# ESC_BOARD.net
KiCad netlist of a schematic drawn in EAGLE
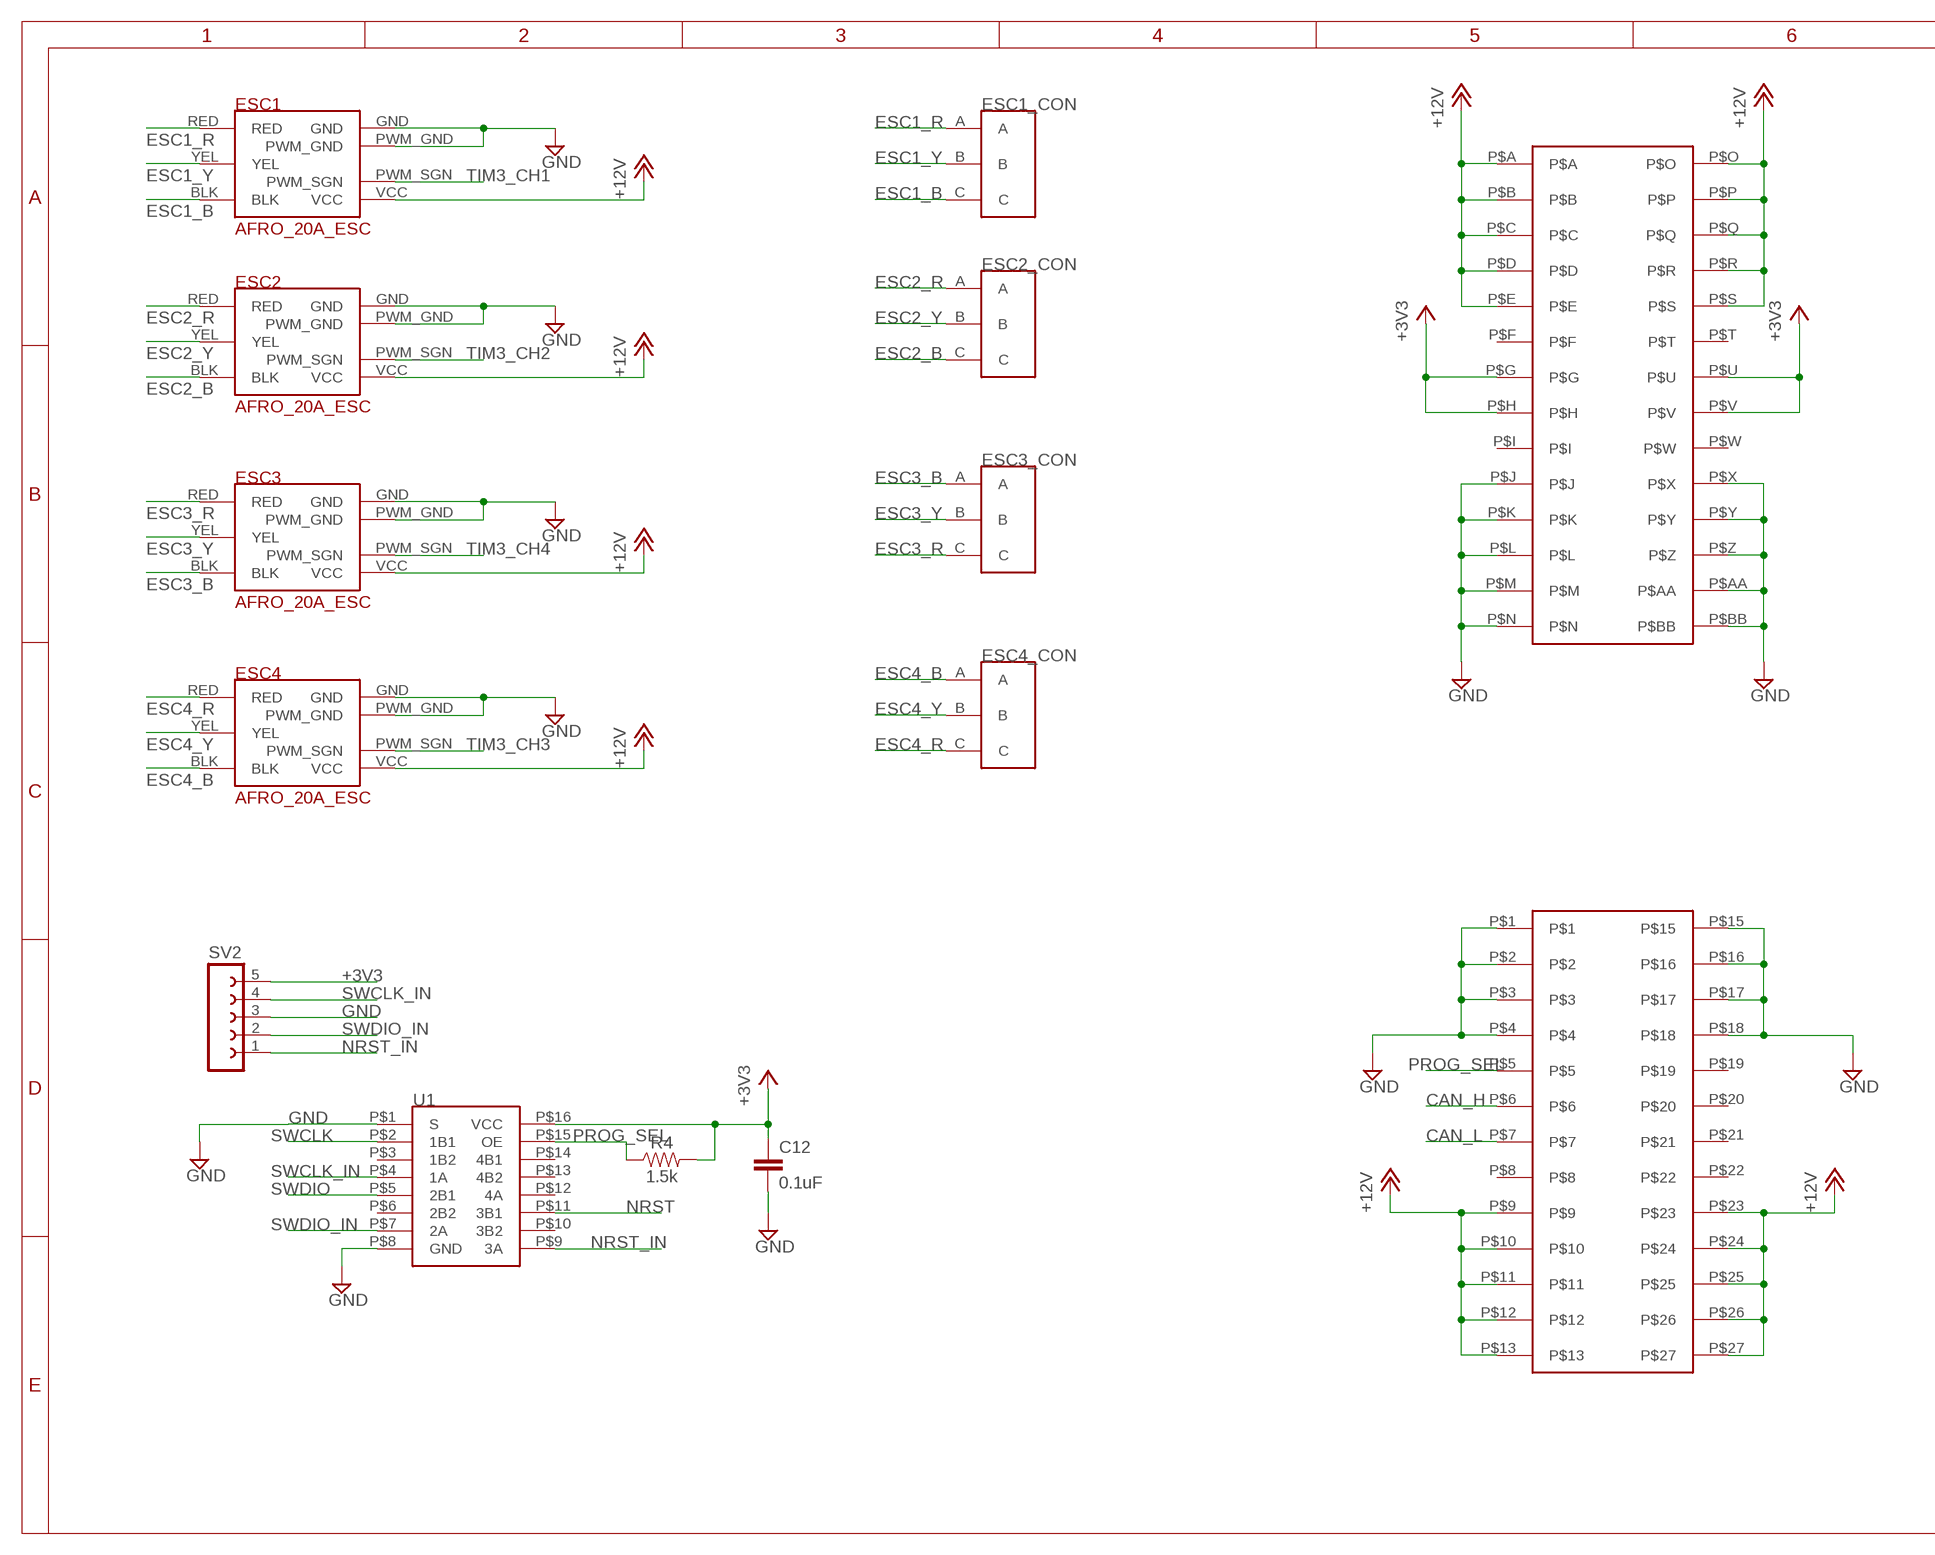
[diagram p0: schematic, sheet 1, part 1 of 2]
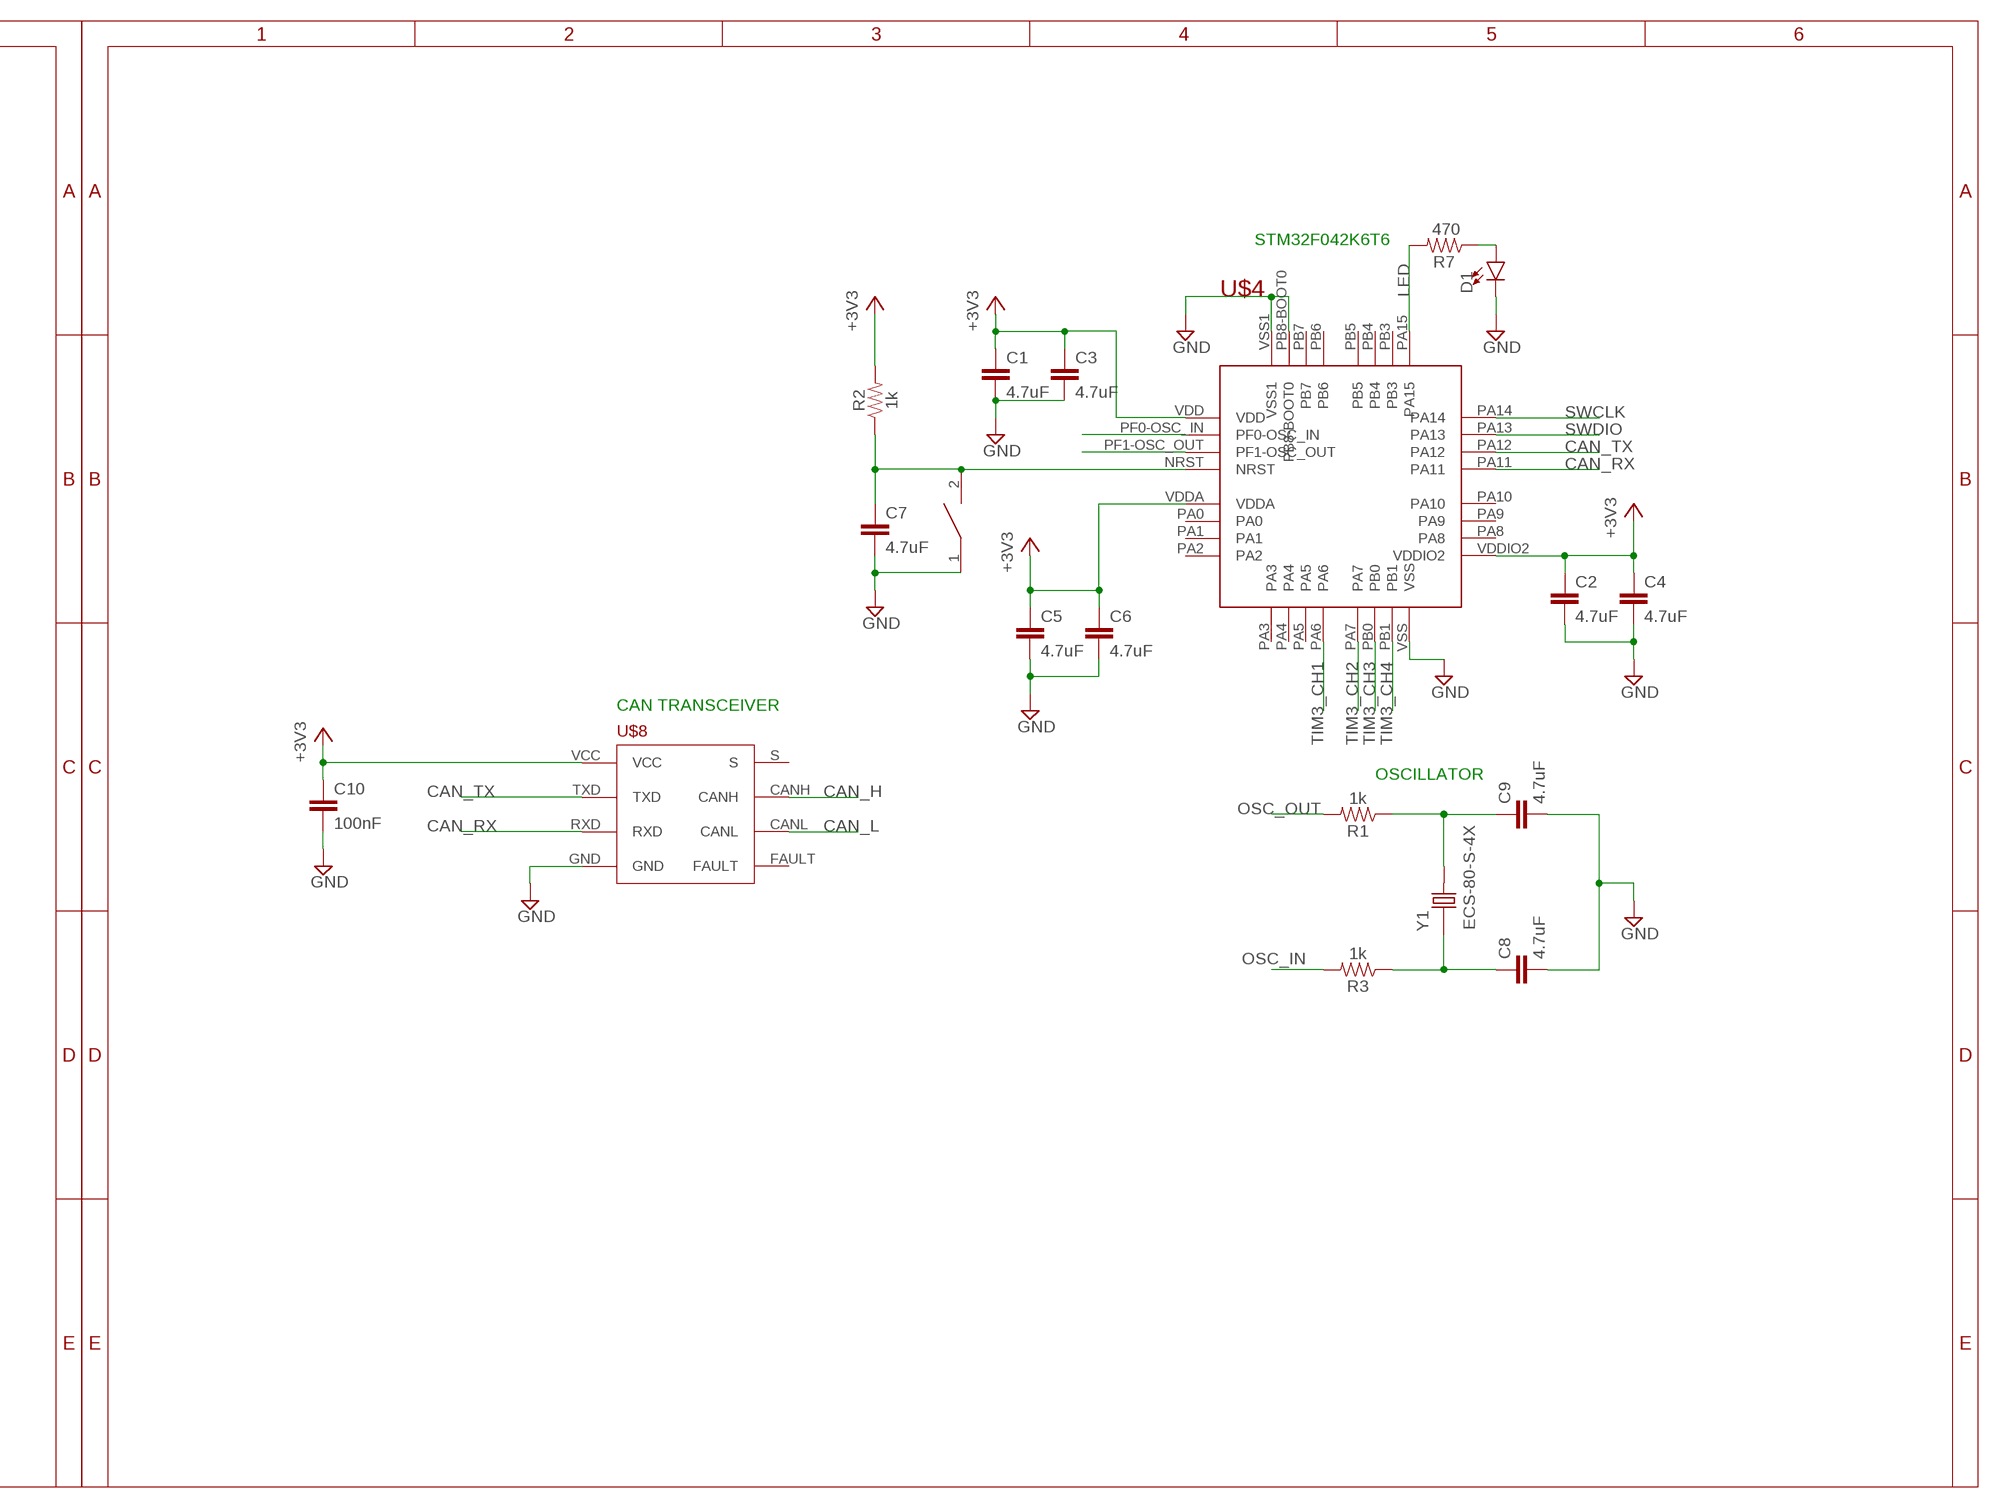
[diagram p1: schematic, sheet 1, part 2 of 2]

(export (version "E")
  (design (tool "Eeschema 10.0.6"))
  (components
    (comp (ref "C1")
      (value "4.7uF")
      (footprint "eagle-import:0603")
      (libsource (lib "eagle-import") (part "4.7UF0603"))
    )
    (comp (ref "C2")
      (value "4.7uF")
      (footprint "eagle-import:0603")
      (libsource (lib "eagle-import") (part "4.7UF0603"))
    )
    (comp (ref "C3")
      (value "4.7uF")
      (footprint "eagle-import:0603")
      (libsource (lib "eagle-import") (part "4.7UF0603"))
    )
    (comp (ref "C4")
      (value "4.7uF")
      (footprint "eagle-import:0603")
      (libsource (lib "eagle-import") (part "4.7UF0603"))
    )
    (comp (ref "C5")
      (value "4.7uF")
      (footprint "eagle-import:0603")
      (libsource (lib "eagle-import") (part "4.7UF0603"))
    )
    (comp (ref "C6")
      (value "4.7uF")
      (footprint "eagle-import:0603")
      (libsource (lib "eagle-import") (part "4.7UF0603"))
    )
    (comp (ref "C7")
      (value "4.7uF")
      (footprint "eagle-import:0603")
      (libsource (lib "eagle-import") (part "4.7UF0603"))
    )
    (comp (ref "C8")
      (value "4.7uF")
      (footprint "eagle-import:0603")
      (libsource (lib "eagle-import") (part "4.7UF0603"))
    )
    (comp (ref "C9")
      (value "4.7uF")
      (footprint "eagle-import:0603")
      (libsource (lib "eagle-import") (part "4.7UF0603"))
    )
    (comp (ref "C10")
      (value "100nF")
      (footprint "eagle-import:0603")
      (libsource (lib "eagle-import") (part "4.7UF0603"))
    )
    (comp (ref "C12")
      (value "0.1uF")
      (footprint "eagle-import:0603")
      (libsource (lib "eagle-import") (part "0.1UF-0603-25V-(+80/-20%)"))
    )
    (comp (ref "D1")
      (value "LED0603")
      (footprint "eagle-import:LED-0603")
      (libsource (lib "eagle-import") (part "LED0603"))
    )
    (comp (ref "ESC1")
      (value "AFRO_20A_ESC")
      (footprint "eagle-import:AFRO_20A_ESC")
      (libsource (lib "eagle-import") (part "AFRO_20A_ESC"))
    )
    (comp (ref "ESC1_CON")
      (value "3PINCONNECTOR")
      (footprint "eagle-import:3PINCONNECTOR")
      (libsource (lib "eagle-import") (part "3PINCONNECTOR"))
    )
    (comp (ref "ESC2")
      (value "AFRO_20A_ESC")
      (footprint "eagle-import:AFRO_20A_ESC")
      (libsource (lib "eagle-import") (part "AFRO_20A_ESC"))
    )
    (comp (ref "ESC2_CON")
      (value "3PINCONNECTOR")
      (footprint "eagle-import:3PINCONNECTOR")
      (libsource (lib "eagle-import") (part "3PINCONNECTOR"))
    )
    (comp (ref "ESC3")
      (value "AFRO_20A_ESC")
      (footprint "eagle-import:AFRO_20A_ESC")
      (libsource (lib "eagle-import") (part "AFRO_20A_ESC"))
    )
    (comp (ref "ESC3_CON")
      (value "3PINCONNECTOR")
      (footprint "eagle-import:3PINCONNECTOR")
      (libsource (lib "eagle-import") (part "3PINCONNECTOR"))
    )
    (comp (ref "ESC4")
      (value "AFRO_20A_ESC")
      (footprint "eagle-import:AFRO_20A_ESC")
      (libsource (lib "eagle-import") (part "AFRO_20A_ESC"))
    )
    (comp (ref "ESC4_CON")
      (value "3PINCONNECTOR")
      (footprint "eagle-import:3PINCONNECTOR")
      (libsource (lib "eagle-import") (part "3PINCONNECTOR"))
    )
    (comp (ref "R1")
      (value "1k")
      (footprint "eagle-import:0603")
      (libsource (lib "eagle-import") (part "1KOHM-0603-1/10W-1%"))
    )
    (comp (ref "R2")
      (value "1k")
      (footprint "eagle-import:0603")
      (libsource (lib "eagle-import") (part "1KOHM-0603-1/10W-1%"))
    )
    (comp (ref "R3")
      (value "1k")
      (footprint "eagle-import:0603")
      (libsource (lib "eagle-import") (part "1KOHM-0603-1/10W-1%"))
    )
    (comp (ref "R4")
      (value "1.5k")
      (footprint "eagle-import:0603")
      (libsource (lib "eagle-import") (part "1.5KOHM-0603-1/10W-1%"))
    )
    (comp (ref "R7")
      (value "470")
      (footprint "eagle-import:0603")
      (libsource (lib "eagle-import") (part "RESISTOR0603"))
    )
    (comp (ref "RESET")
      (value "SWITCH")
      (footprint "eagle-import:SW_2512")
      (libsource (lib "eagle-import") (part "SWITCH"))
    )
    (comp (ref "SV2")
      (value "FE05-1")
      (footprint "eagle-import:FE05-1")
      (libsource (lib "eagle-import") (part "FE05-1"))
    )
    (comp (ref "U$1")
      (value "ESC2BACKPLANE")
      (footprint "eagle-import:ESC2BACKPLANE_WHOLE")
      (libsource (lib "eagle-import") (part "ESC2BACKPLANE"))
    )
    (comp (ref "U$4")
      (value "STM32F042K6T6")
      (footprint "eagle-import:STM32F042K6T6")
      (libsource (lib "eagle-import") (part "STM32F042K6T6"))
    )
    (comp (ref "U$8")
      (value "TCAN337D")
      (footprint "eagle-import:TCAN337D")
      (libsource (lib "eagle-import") (part "TCAN337D"))
    )
    (comp (ref "U1")
      (value "SN74CBTLV3257PWR")
      (footprint "eagle-import:SN74CBTLV3257PWR")
      (libsource (lib "eagle-import") (part "SN74CBTLV3257PWR"))
    )
    (comp (ref "Y1")
      (value "ECS-80-S-4X")
      (footprint "eagle-import:XTAL_ECS-80-S-4X")
      (fields (field (name "DIGI-KEY_PART_NUMBER") "X1057-ND") (field (name "MF") "ECS International"))
      (libsource (lib "eagle-import") (part "ECS-80-S-4X"))
    )
  )
  (nets
    (net (code "1") (name "+3V3") (class "Default")
      (node (ref "C1") (pin "1") (pinfunction "1_1") (pintype "passive"))
      (node (ref "C10") (pin "1") (pinfunction "1_1") (pintype "passive"))
      (node (ref "C12") (pin "1") (pinfunction "1_1") (pintype "passive"))
      (node (ref "C2") (pin "1") (pinfunction "1_1") (pintype "passive"))
      (node (ref "C3") (pin "1") (pinfunction "1_1") (pintype "passive"))
      (node (ref "C4") (pin "1") (pinfunction "1_1") (pintype "passive"))
      (node (ref "C5") (pin "1") (pinfunction "1_1") (pintype "passive"))
      (node (ref "C6") (pin "1") (pinfunction "1_1") (pintype "passive"))
      (node (ref "R2") (pin "2") (pinfunction "2_2") (pintype "passive"))
      (node (ref "R4") (pin "2") (pinfunction "2_2") (pintype "passive"))
      (node (ref "SV2") (pin "5") (pinfunction "5_5") (pintype "passive"))
      (node (ref "U$1") (pin "P$G") (pinfunction "P$G_P$G") (pintype "bidirectional"))
      (node (ref "U$1") (pin "P$H") (pinfunction "P$H_P$H") (pintype "bidirectional"))
      (node (ref "U$1") (pin "P$U") (pinfunction "P$U_P$U") (pintype "bidirectional"))
      (node (ref "U$1") (pin "P$V") (pinfunction "P$V_P$V") (pintype "bidirectional"))
      (node (ref "U$4") (pin "VDD") (pinfunction "VDD_VDD") (pintype "bidirectional"))
      (node (ref "U$4") (pin "VDDA") (pinfunction "VDDA_VDDA") (pintype "bidirectional"))
      (node (ref "U$4") (pin "VDDIO2") (pinfunction "VDDIO2_VDDIO2") (pintype "bidirectional"))
      (node (ref "U$8") (pin "VCC") (pinfunction "VCC_VCC") (pintype "bidirectional"))
      (node (ref "U1") (pin "P$16") (pinfunction "VCC_P$16") (pintype "bidirectional"))
    )
    (net (code "2") (name "+12V") (class "Default")
      (node (ref "ESC1") (pin "VCC") (pinfunction "VCC_VCC") (pintype "bidirectional"))
      (node (ref "ESC2") (pin "VCC") (pinfunction "VCC_VCC") (pintype "bidirectional"))
      (node (ref "ESC3") (pin "VCC") (pinfunction "VCC_VCC") (pintype "bidirectional"))
      (node (ref "ESC4") (pin "VCC") (pinfunction "VCC_VCC") (pintype "bidirectional"))
      (node (ref "U$1") (pin "P$10") (pinfunction "P$10_P$10") (pintype "bidirectional"))
      (node (ref "U$1") (pin "P$11") (pinfunction "P$11_P$11") (pintype "bidirectional"))
      (node (ref "U$1") (pin "P$12") (pinfunction "P$12_P$12") (pintype "bidirectional"))
      (node (ref "U$1") (pin "P$13") (pinfunction "P$13_P$13") (pintype "bidirectional"))
      (node (ref "U$1") (pin "P$23") (pinfunction "P$23_P$23") (pintype "bidirectional"))
      (node (ref "U$1") (pin "P$24") (pinfunction "P$24_P$24") (pintype "bidirectional"))
      (node (ref "U$1") (pin "P$25") (pinfunction "P$25_P$25") (pintype "bidirectional"))
      (node (ref "U$1") (pin "P$26") (pinfunction "P$26_P$26") (pintype "bidirectional"))
      (node (ref "U$1") (pin "P$27") (pinfunction "P$27_P$27") (pintype "bidirectional"))
      (node (ref "U$1") (pin "P$9") (pinfunction "P$9_P$9") (pintype "bidirectional"))
      (node (ref "U$1") (pin "P$A") (pinfunction "P$A_P$A") (pintype "bidirectional"))
      (node (ref "U$1") (pin "P$B") (pinfunction "P$B_P$B") (pintype "bidirectional"))
      (node (ref "U$1") (pin "P$C") (pinfunction "P$C_P$C") (pintype "bidirectional"))
      (node (ref "U$1") (pin "P$D") (pinfunction "P$D_P$D") (pintype "bidirectional"))
      (node (ref "U$1") (pin "P$E") (pinfunction "P$E_P$E") (pintype "bidirectional"))
      (node (ref "U$1") (pin "P$O") (pinfunction "P$O_P$O") (pintype "bidirectional"))
      (node (ref "U$1") (pin "P$P") (pinfunction "P$P_P$P") (pintype "bidirectional"))
      (node (ref "U$1") (pin "P$Q") (pinfunction "P$Q_P$Q") (pintype "bidirectional"))
      (node (ref "U$1") (pin "P$R") (pinfunction "P$R_P$R") (pintype "bidirectional"))
      (node (ref "U$1") (pin "P$S") (pinfunction "P$S_P$S") (pintype "bidirectional"))
    )
    (net (code "3") (name "/CAN_H") (class "Default")
      (node (ref "U$1") (pin "P$6") (pinfunction "P$6_P$6") (pintype "bidirectional"))
      (node (ref "U$8") (pin "CANH") (pinfunction "CANH_CANH") (pintype "bidirectional"))
    )
    (net (code "4") (name "/CAN_L") (class "Default")
      (node (ref "U$1") (pin "P$7") (pinfunction "P$7_P$7") (pintype "bidirectional"))
      (node (ref "U$8") (pin "CANL") (pinfunction "CANL_CANL") (pintype "bidirectional"))
    )
    (net (code "5") (name "/CAN_RX") (class "Default")
      (node (ref "U$4") (pin "PA11") (pinfunction "PA11_PA11") (pintype "bidirectional"))
      (node (ref "U$8") (pin "RXD") (pinfunction "RXD_RXD") (pintype "bidirectional"))
    )
    (net (code "6") (name "/CAN_TX") (class "Default")
      (node (ref "U$4") (pin "PA12") (pinfunction "PA12_PA12") (pintype "bidirectional"))
      (node (ref "U$8") (pin "TXD") (pinfunction "TXD_TXD") (pintype "bidirectional"))
    )
    (net (code "7") (name "/ESC1_B") (class "Default")
      (node (ref "ESC1") (pin "BLK") (pinfunction "BLK_BLK") (pintype "bidirectional"))
      (node (ref "ESC1_CON") (pin "C") (pinfunction "C_C") (pintype "bidirectional"))
    )
    (net (code "8") (name "/ESC1_R") (class "Default")
      (node (ref "ESC1") (pin "RED") (pinfunction "RED_RED") (pintype "bidirectional"))
      (node (ref "ESC1_CON") (pin "A") (pinfunction "A_A") (pintype "bidirectional"))
    )
    (net (code "9") (name "/ESC1_Y") (class "Default")
      (node (ref "ESC1") (pin "YEL") (pinfunction "YEL_YEL") (pintype "bidirectional"))
      (node (ref "ESC1_CON") (pin "B") (pinfunction "B_B") (pintype "bidirectional"))
    )
    (net (code "10") (name "/ESC2_B") (class "Default")
      (node (ref "ESC2") (pin "BLK") (pinfunction "BLK_BLK") (pintype "bidirectional"))
      (node (ref "ESC2_CON") (pin "C") (pinfunction "C_C") (pintype "bidirectional"))
    )
    (net (code "11") (name "/ESC2_R") (class "Default")
      (node (ref "ESC2") (pin "RED") (pinfunction "RED_RED") (pintype "bidirectional"))
      (node (ref "ESC2_CON") (pin "A") (pinfunction "A_A") (pintype "bidirectional"))
    )
    (net (code "12") (name "/ESC2_Y") (class "Default")
      (node (ref "ESC2") (pin "YEL") (pinfunction "YEL_YEL") (pintype "bidirectional"))
      (node (ref "ESC2_CON") (pin "B") (pinfunction "B_B") (pintype "bidirectional"))
    )
    (net (code "13") (name "/ESC3_B") (class "Default")
      (node (ref "ESC3") (pin "BLK") (pinfunction "BLK_BLK") (pintype "bidirectional"))
      (node (ref "ESC3_CON") (pin "A") (pinfunction "A_A") (pintype "bidirectional"))
    )
    (net (code "14") (name "/ESC3_R") (class "Default")
      (node (ref "ESC3") (pin "RED") (pinfunction "RED_RED") (pintype "bidirectional"))
      (node (ref "ESC3_CON") (pin "C") (pinfunction "C_C") (pintype "bidirectional"))
    )
    (net (code "15") (name "/ESC3_Y") (class "Default")
      (node (ref "ESC3") (pin "YEL") (pinfunction "YEL_YEL") (pintype "bidirectional"))
      (node (ref "ESC3_CON") (pin "B") (pinfunction "B_B") (pintype "bidirectional"))
    )
    (net (code "16") (name "/ESC4_B") (class "Default")
      (node (ref "ESC4") (pin "BLK") (pinfunction "BLK_BLK") (pintype "bidirectional"))
      (node (ref "ESC4_CON") (pin "A") (pinfunction "A_A") (pintype "bidirectional"))
    )
    (net (code "17") (name "/ESC4_R") (class "Default")
      (node (ref "ESC4") (pin "RED") (pinfunction "RED_RED") (pintype "bidirectional"))
      (node (ref "ESC4_CON") (pin "C") (pinfunction "C_C") (pintype "bidirectional"))
    )
    (net (code "18") (name "/ESC4_Y") (class "Default")
      (node (ref "ESC4") (pin "YEL") (pinfunction "YEL_YEL") (pintype "bidirectional"))
      (node (ref "ESC4_CON") (pin "B") (pinfunction "B_B") (pintype "bidirectional"))
    )
    (net (code "19") (name "/LED") (class "Default")
      (node (ref "R7") (pin "2") (pinfunction "2_2") (pintype "passive"))
      (node (ref "U$4") (pin "PA15") (pinfunction "PA15_PA15") (pintype "bidirectional"))
    )
    (net (code "20") (name "/NRST") (class "Default")
      (node (ref "C7") (pin "1") (pinfunction "1_1") (pintype "passive"))
      (node (ref "R2") (pin "1") (pinfunction "1_1") (pintype "passive"))
      (node (ref "RESET") (pin "2") (pinfunction "P$2_2") (pintype "bidirectional"))
      (node (ref "U$4") (pin "NRST") (pinfunction "NRST_NRST") (pintype "bidirectional"))
      (node (ref "U1") (pin "P$11") (pinfunction "3B1_P$11") (pintype "bidirectional"))
    )
    (net (code "21") (name "/NRST_IN") (class "Default")
      (node (ref "SV2") (pin "1") (pinfunction "1_1") (pintype "passive"))
      (node (ref "U1") (pin "P$9") (pinfunction "3A_P$9") (pintype "bidirectional"))
    )
    (net (code "22") (name "/OSC_IN") (class "Default")
      (node (ref "R3") (pin "2") (pinfunction "2_2") (pintype "passive"))
      (node (ref "U$4") (pin "PF0-OSC_IN") (pinfunction "PF0-OSC_IN_PF0-OSC_IN") (pintype "bidirectional"))
    )
    (net (code "23") (name "/OSC_OUT") (class "Default")
      (node (ref "R1") (pin "2") (pinfunction "2_2") (pintype "passive"))
      (node (ref "U$4") (pin "PF1-OSC_OUT") (pinfunction "PF1-OSC_OUT_PF1-OSC_OUT") (pintype "bidirectional"))
    )
    (net (code "24") (name "/PROG_SEL") (class "Default")
      (node (ref "R4") (pin "1") (pinfunction "1_1") (pintype "passive"))
      (node (ref "U$1") (pin "P$5") (pinfunction "P$5_P$5") (pintype "bidirectional"))
      (node (ref "U1") (pin "P$15") (pinfunction "OE_P$15") (pintype "bidirectional"))
    )
    (net (code "25") (name "/SWCLK") (class "Default")
      (node (ref "U$4") (pin "PA14") (pinfunction "PA14_PA14") (pintype "bidirectional"))
      (node (ref "U1") (pin "P$2") (pinfunction "1B1_P$2") (pintype "bidirectional"))
    )
    (net (code "26") (name "/SWCLK_IN") (class "Default")
      (node (ref "SV2") (pin "4") (pinfunction "4_4") (pintype "passive"))
      (node (ref "U1") (pin "P$4") (pinfunction "1A_P$4") (pintype "bidirectional"))
    )
    (net (code "27") (name "/SWDIO") (class "Default")
      (node (ref "U$4") (pin "PA13") (pinfunction "PA13_PA13") (pintype "bidirectional"))
      (node (ref "U1") (pin "P$5") (pinfunction "2B1_P$5") (pintype "bidirectional"))
    )
    (net (code "28") (name "/SWDIO_IN") (class "Default")
      (node (ref "SV2") (pin "2") (pinfunction "2_2") (pintype "passive"))
      (node (ref "U1") (pin "P$7") (pinfunction "2A_P$7") (pintype "bidirectional"))
    )
    (net (code "29") (name "/TIM3_CH1") (class "Default")
      (node (ref "ESC1") (pin "PWM_SGN") (pinfunction "PWM_SGN_PWM_SGN") (pintype "bidirectional"))
      (node (ref "U$4") (pin "PA6") (pinfunction "PA6_PA6") (pintype "bidirectional"))
    )
    (net (code "30") (name "/TIM3_CH2") (class "Default")
      (node (ref "ESC2") (pin "PWM_SGN") (pinfunction "PWM_SGN_PWM_SGN") (pintype "bidirectional"))
      (node (ref "U$4") (pin "PA7") (pinfunction "PA7_PA7") (pintype "bidirectional"))
    )
    (net (code "31") (name "/TIM3_CH3") (class "Default")
      (node (ref "ESC4") (pin "PWM_SGN") (pinfunction "PWM_SGN_PWM_SGN") (pintype "bidirectional"))
      (node (ref "U$4") (pin "PB0") (pinfunction "PB0_PB0") (pintype "bidirectional"))
    )
    (net (code "32") (name "/TIM3_CH4") (class "Default")
      (node (ref "ESC3") (pin "PWM_SGN") (pinfunction "PWM_SGN_PWM_SGN") (pintype "bidirectional"))
      (node (ref "U$4") (pin "PB1") (pinfunction "PB1_PB1") (pintype "bidirectional"))
    )
    (net (code "33") (name "GND") (class "Default")
      (node (ref "C1") (pin "2") (pinfunction "2_2") (pintype "passive"))
      (node (ref "C10") (pin "2") (pinfunction "2_2") (pintype "passive"))
      (node (ref "C12") (pin "2") (pinfunction "2_2") (pintype "passive"))
      (node (ref "C2") (pin "2") (pinfunction "2_2") (pintype "passive"))
      (node (ref "C3") (pin "2") (pinfunction "2_2") (pintype "passive"))
      (node (ref "C4") (pin "2") (pinfunction "2_2") (pintype "passive"))
      (node (ref "C5") (pin "2") (pinfunction "2_2") (pintype "passive"))
      (node (ref "C6") (pin "2") (pinfunction "2_2") (pintype "passive"))
      (node (ref "C7") (pin "2") (pinfunction "2_2") (pintype "passive"))
      (node (ref "C8") (pin "2") (pinfunction "2_2") (pintype "passive"))
      (node (ref "C9") (pin "2") (pinfunction "2_2") (pintype "passive"))
      (node (ref "D1") (pin "C") (pinfunction "C_C") (pintype "passive"))
      (node (ref "ESC1") (pin "GND") (pinfunction "GND_GND") (pintype "bidirectional"))
      (node (ref "ESC1") (pin "PWM_GND") (pinfunction "PWM_GND_PWM_GND") (pintype "bidirectional"))
      (node (ref "ESC2") (pin "GND") (pinfunction "GND_GND") (pintype "bidirectional"))
      (node (ref "ESC2") (pin "PWM_GND") (pinfunction "PWM_GND_PWM_GND") (pintype "bidirectional"))
      (node (ref "ESC3") (pin "GND") (pinfunction "GND_GND") (pintype "bidirectional"))
      (node (ref "ESC3") (pin "PWM_GND") (pinfunction "PWM_GND_PWM_GND") (pintype "bidirectional"))
      (node (ref "ESC4") (pin "GND") (pinfunction "GND_GND") (pintype "bidirectional"))
      (node (ref "ESC4") (pin "PWM_GND") (pinfunction "PWM_GND_PWM_GND") (pintype "bidirectional"))
      (node (ref "RESET") (pin "1") (pinfunction "P$1_1") (pintype "bidirectional"))
      (node (ref "SV2") (pin "3") (pinfunction "3_3") (pintype "passive"))
      (node (ref "U$1") (pin "P$1") (pinfunction "P$1_P$1") (pintype "bidirectional"))
      (node (ref "U$1") (pin "P$15") (pinfunction "P$15_P$15") (pintype "bidirectional"))
      (node (ref "U$1") (pin "P$16") (pinfunction "P$16_P$16") (pintype "bidirectional"))
      (node (ref "U$1") (pin "P$17") (pinfunction "P$17_P$17") (pintype "bidirectional"))
      (node (ref "U$1") (pin "P$18") (pinfunction "P$18_P$18") (pintype "bidirectional"))
      (node (ref "U$1") (pin "P$2") (pinfunction "P$2_P$2") (pintype "bidirectional"))
      (node (ref "U$1") (pin "P$3") (pinfunction "P$3_P$3") (pintype "bidirectional"))
      (node (ref "U$1") (pin "P$4") (pinfunction "P$4_P$4") (pintype "bidirectional"))
      (node (ref "U$1") (pin "P$AA") (pinfunction "P$AA_P$AA") (pintype "bidirectional"))
      (node (ref "U$1") (pin "P$BB") (pinfunction "P$BB_P$BB") (pintype "bidirectional"))
      (node (ref "U$1") (pin "P$J") (pinfunction "P$J_P$J") (pintype "bidirectional"))
      (node (ref "U$1") (pin "P$K") (pinfunction "P$K_P$K") (pintype "bidirectional"))
      (node (ref "U$1") (pin "P$L") (pinfunction "P$L_P$L") (pintype "bidirectional"))
      (node (ref "U$1") (pin "P$M") (pinfunction "P$M_P$M") (pintype "bidirectional"))
      (node (ref "U$1") (pin "P$N") (pinfunction "P$N_P$N") (pintype "bidirectional"))
      (node (ref "U$1") (pin "P$X") (pinfunction "P$X_P$X") (pintype "bidirectional"))
      (node (ref "U$1") (pin "P$Y") (pinfunction "P$Y_P$Y") (pintype "bidirectional"))
      (node (ref "U$1") (pin "P$Z") (pinfunction "P$Z_P$Z") (pintype "bidirectional"))
      (node (ref "U$4") (pin "PB8-BOOT0") (pinfunction "PB8-BOOT0_PB8-BOOT0") (pintype "bidirectional"))
      (node (ref "U$4") (pin "VSS") (pinfunction "VSS_VSS") (pintype "bidirectional"))
      (node (ref "U$4") (pin "VSS1") (pinfunction "VSS1_VSS1") (pintype "bidirectional"))
      (node (ref "U$8") (pin "GND") (pinfunction "GND_GND") (pintype "bidirectional"))
      (node (ref "U1") (pin "P$1") (pinfunction "S_P$1") (pintype "bidirectional"))
      (node (ref "U1") (pin "P$8") (pinfunction "GND_P$8") (pintype "bidirectional"))
    )
    (net (code "34") (name "Net-(C8-Pad1)") (class "Default")
      (node (ref "C8") (pin "1") (pinfunction "1_1") (pintype "passive"))
      (node (ref "R3") (pin "1") (pinfunction "1_1") (pintype "passive"))
      (node (ref "Y1") (pin "1") (pinfunction "1_1") (pintype "passive"))
    )
    (net (code "35") (name "Net-(C9-Pad1)") (class "Default")
      (node (ref "C9") (pin "1") (pinfunction "1_1") (pintype "passive"))
      (node (ref "R1") (pin "1") (pinfunction "1_1") (pintype "passive"))
      (node (ref "Y1") (pin "2") (pinfunction "2_2") (pintype "passive"))
    )
    (net (code "36") (name "Net-(D1-PadA)") (class "Default")
      (node (ref "D1") (pin "A") (pinfunction "A_A") (pintype "passive"))
      (node (ref "R7") (pin "1") (pinfunction "1_1") (pintype "passive"))
    )
    (net (code "37") (name "unconnected-(U$1-PadP$8)") (class "Default")
      (node (ref "U$1") (pin "P$8") (pinfunction "P$8_P$8") (pintype "bidirectional"))
    )
    (net (code "38") (name "unconnected-(U$1-PadP$19)") (class "Default")
      (node (ref "U$1") (pin "P$19") (pinfunction "P$19_P$19") (pintype "bidirectional"))
    )
    (net (code "39") (name "unconnected-(U$1-PadP$20)") (class "Default")
      (node (ref "U$1") (pin "P$20") (pinfunction "P$20_P$20") (pintype "bidirectional"))
    )
    (net (code "40") (name "unconnected-(U$1-PadP$21)") (class "Default")
      (node (ref "U$1") (pin "P$21") (pinfunction "P$21_P$21") (pintype "bidirectional"))
    )
    (net (code "41") (name "unconnected-(U$1-PadP$22)") (class "Default")
      (node (ref "U$1") (pin "P$22") (pinfunction "P$22_P$22") (pintype "bidirectional"))
    )
    (net (code "42") (name "unconnected-(U$1-PadP$F)") (class "Default")
      (node (ref "U$1") (pin "P$F") (pinfunction "P$F_P$F") (pintype "bidirectional"))
    )
    (net (code "43") (name "unconnected-(U$1-PadP$I)") (class "Default")
      (node (ref "U$1") (pin "P$I") (pinfunction "P$I_P$I") (pintype "bidirectional"))
    )
    (net (code "44") (name "unconnected-(U$1-PadP$T)") (class "Default")
      (node (ref "U$1") (pin "P$T") (pinfunction "P$T_P$T") (pintype "bidirectional"))
    )
    (net (code "45") (name "unconnected-(U$1-PadP$W)") (class "Default")
      (node (ref "U$1") (pin "P$W") (pinfunction "P$W_P$W") (pintype "bidirectional"))
    )
    (net (code "46") (name "unconnected-(U$4-PadPA0)") (class "Default")
      (node (ref "U$4") (pin "PA0") (pinfunction "PA0_PA0") (pintype "bidirectional"))
    )
    (net (code "47") (name "unconnected-(U$4-PadPA1)") (class "Default")
      (node (ref "U$4") (pin "PA1") (pinfunction "PA1_PA1") (pintype "bidirectional"))
    )
    (net (code "48") (name "unconnected-(U$4-PadPA2)") (class "Default")
      (node (ref "U$4") (pin "PA2") (pinfunction "PA2_PA2") (pintype "bidirectional"))
    )
    (net (code "49") (name "unconnected-(U$4-PadPA3)") (class "Default")
      (node (ref "U$4") (pin "PA3") (pinfunction "PA3_PA3") (pintype "bidirectional"))
    )
    (net (code "50") (name "unconnected-(U$4-PadPA4)") (class "Default")
      (node (ref "U$4") (pin "PA4") (pinfunction "PA4_PA4") (pintype "bidirectional"))
    )
    (net (code "51") (name "unconnected-(U$4-PadPA5)") (class "Default")
      (node (ref "U$4") (pin "PA5") (pinfunction "PA5_PA5") (pintype "bidirectional"))
    )
    (net (code "52") (name "unconnected-(U$4-PadPA8)") (class "Default")
      (node (ref "U$4") (pin "PA8") (pinfunction "PA8_PA8") (pintype "bidirectional"))
    )
    (net (code "53") (name "unconnected-(U$4-PadPA9)") (class "Default")
      (node (ref "U$4") (pin "PA9") (pinfunction "PA9_PA9") (pintype "bidirectional"))
    )
    (net (code "54") (name "unconnected-(U$4-PadPA10)") (class "Default")
      (node (ref "U$4") (pin "PA10") (pinfunction "PA10_PA10") (pintype "bidirectional"))
    )
    (net (code "55") (name "unconnected-(U$4-PadPB3)") (class "Default")
      (node (ref "U$4") (pin "PB3") (pinfunction "PB3_PB3") (pintype "bidirectional"))
    )
    (net (code "56") (name "unconnected-(U$4-PadPB4)") (class "Default")
      (node (ref "U$4") (pin "PB4") (pinfunction "PB4_PB4") (pintype "bidirectional"))
    )
    (net (code "57") (name "unconnected-(U$4-PadPB5)") (class "Default")
      (node (ref "U$4") (pin "PB5") (pinfunction "PB5_PB5") (pintype "bidirectional"))
    )
    (net (code "58") (name "unconnected-(U$4-PadPB6)") (class "Default")
      (node (ref "U$4") (pin "PB6") (pinfunction "PB6_PB6") (pintype "bidirectional"))
    )
    (net (code "59") (name "unconnected-(U$4-PadPB7)") (class "Default")
      (node (ref "U$4") (pin "PB7") (pinfunction "PB7_PB7") (pintype "bidirectional"))
    )
    (net (code "60") (name "unconnected-(U$8-PadFAULT)") (class "Default")
      (node (ref "U$8") (pin "FAULT") (pinfunction "FAULT_FAULT") (pintype "bidirectional"))
    )
    (net (code "61") (name "unconnected-(U$8-PadS)") (class "Default")
      (node (ref "U$8") (pin "S") (pinfunction "S_S") (pintype "bidirectional"))
    )
    (net (code "62") (name "unconnected-(U1-1B2-PadP$3)") (class "Default")
      (node (ref "U1") (pin "P$3") (pinfunction "1B2_P$3") (pintype "bidirectional"))
    )
    (net (code "63") (name "unconnected-(U1-2B2-PadP$6)") (class "Default")
      (node (ref "U1") (pin "P$6") (pinfunction "2B2_P$6") (pintype "bidirectional"))
    )
    (net (code "64") (name "unconnected-(U1-3B2-PadP$10)") (class "Default")
      (node (ref "U1") (pin "P$10") (pinfunction "3B2_P$10") (pintype "bidirectional"))
    )
    (net (code "65") (name "unconnected-(U1-4A-PadP$12)") (class "Default")
      (node (ref "U1") (pin "P$12") (pinfunction "4A_P$12") (pintype "bidirectional"))
    )
    (net (code "66") (name "unconnected-(U1-4B1-PadP$14)") (class "Default")
      (node (ref "U1") (pin "P$14") (pinfunction "4B1_P$14") (pintype "bidirectional"))
    )
    (net (code "67") (name "unconnected-(U1-4B2-PadP$13)") (class "Default")
      (node (ref "U1") (pin "P$13") (pinfunction "4B2_P$13") (pintype "bidirectional"))
    )
  )
)
